# RFM12B-Breakout-v10.net
KiCad netlist of a schematic drawn in EAGLE
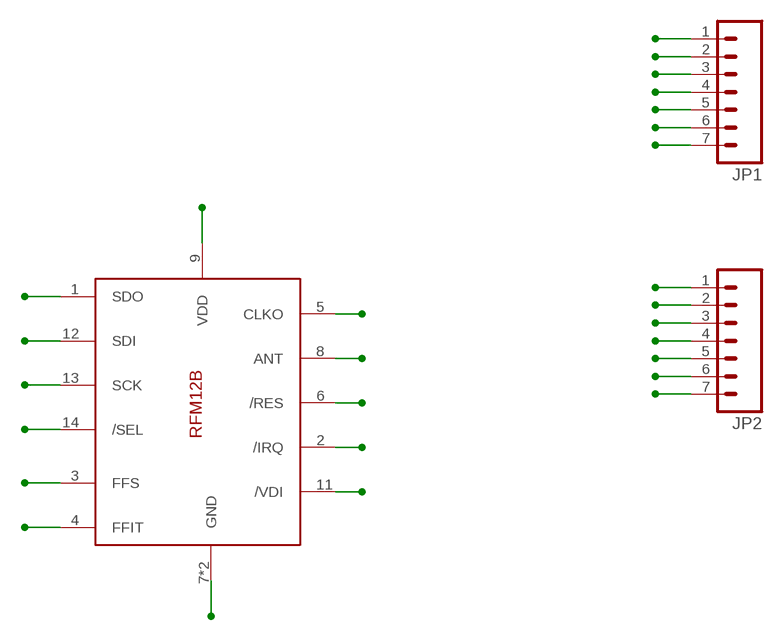
[diagram p0: schematic, sheet 1]

(export (version "E")
  (design (tool "Eeschema 10.0.6"))
  (components
    (comp (ref "JP1")
      (value "M07LONGPADS")
      (footprint "eagle-import:1X07_LONGPADS")
      (libsource (lib "eagle-import") (part "M07LONGPADS"))
    )
    (comp (ref "JP2")
      (value "M07LONGPADS")
      (footprint "eagle-import:1X07_LONGPADS")
      (libsource (lib "eagle-import") (part "M07LONGPADS"))
    )
    (comp (ref "U$1")
      (value "RFM12B")
      (footprint "eagle-import:RFM12B-MODULE")
      (libsource (lib "eagle-import") (part "RFM12B"))
    )
  )
  (nets
    (net (code "1") (name "/ANT") (class "Default")
      (node (ref "JP2") (pin "7") (pinfunction "7_7") (pintype "passive"))
      (node (ref "U$1") (pin "8") (pinfunction "ANT_8") (pintype "bidirectional"))
    )
    (net (code "2") (name "/CLKO") (class "Default")
      (node (ref "JP1") (pin "5") (pinfunction "5_5") (pintype "passive"))
      (node (ref "U$1") (pin "5") (pinfunction "CLKO_5") (pintype "bidirectional"))
    )
    (net (code "3") (name "/FFIT") (class "Default")
      (node (ref "JP1") (pin "4") (pinfunction "4_4") (pintype "passive"))
      (node (ref "U$1") (pin "4") (pinfunction "FFIT_4") (pintype "bidirectional"))
    )
    (net (code "4") (name "/FFS") (class "Default")
      (node (ref "JP1") (pin "3") (pinfunction "3_3") (pintype "passive"))
      (node (ref "U$1") (pin "3") (pinfunction "FFS_3") (pintype "bidirectional"))
    )
    (net (code "5") (name "/GND") (class "Default")
      (node (ref "JP1") (pin "7") (pinfunction "7_7") (pintype "passive"))
      (node (ref "JP2") (pin "5") (pinfunction "5_5") (pintype "passive"))
      (node (ref "U$1") (pin "10") (pinfunction "GND_10") (pintype "bidirectional"))
      (node (ref "U$1") (pin "7") (pinfunction "GND_7") (pintype "bidirectional"))
    )
    (net (code "6") (name "/IRQ") (class "Default")
      (node (ref "JP1") (pin "2") (pinfunction "2_2") (pintype "passive"))
      (node (ref "U$1") (pin "2") (pinfunction "/IRQ_2") (pintype "bidirectional"))
    )
    (net (code "7") (name "/RES") (class "Default")
      (node (ref "JP1") (pin "6") (pinfunction "6_6") (pintype "passive"))
      (node (ref "U$1") (pin "6") (pinfunction "/RES_6") (pintype "bidirectional"))
    )
    (net (code "8") (name "/SCK") (class "Default")
      (node (ref "JP2") (pin "2") (pinfunction "2_2") (pintype "passive"))
      (node (ref "U$1") (pin "13") (pinfunction "SCK_13") (pintype "bidirectional"))
    )
    (net (code "9") (name "/SDI") (class "Default")
      (node (ref "JP2") (pin "3") (pinfunction "3_3") (pintype "passive"))
      (node (ref "U$1") (pin "12") (pinfunction "SDI_12") (pintype "bidirectional"))
    )
    (net (code "10") (name "/SDO") (class "Default")
      (node (ref "JP1") (pin "1") (pinfunction "1_1") (pintype "passive"))
      (node (ref "U$1") (pin "1") (pinfunction "SDO_1") (pintype "bidirectional"))
    )
    (net (code "11") (name "/SEL") (class "Default")
      (node (ref "JP2") (pin "1") (pinfunction "1_1") (pintype "passive"))
      (node (ref "U$1") (pin "14") (pinfunction "/SEL_14") (pintype "bidirectional"))
    )
    (net (code "12") (name "/VDD") (class "Default")
      (node (ref "JP2") (pin "6") (pinfunction "6_6") (pintype "passive"))
      (node (ref "U$1") (pin "9") (pinfunction "VDD_9") (pintype "bidirectional"))
    )
    (net (code "13") (name "/VDI") (class "Default")
      (node (ref "JP2") (pin "4") (pinfunction "4_4") (pintype "passive"))
      (node (ref "U$1") (pin "11") (pinfunction "/VDI_11") (pintype "bidirectional"))
    )
  )
)
